# Bluetooth_NRF.net
KiCad netlist of a schematic drawn in Altium Designer
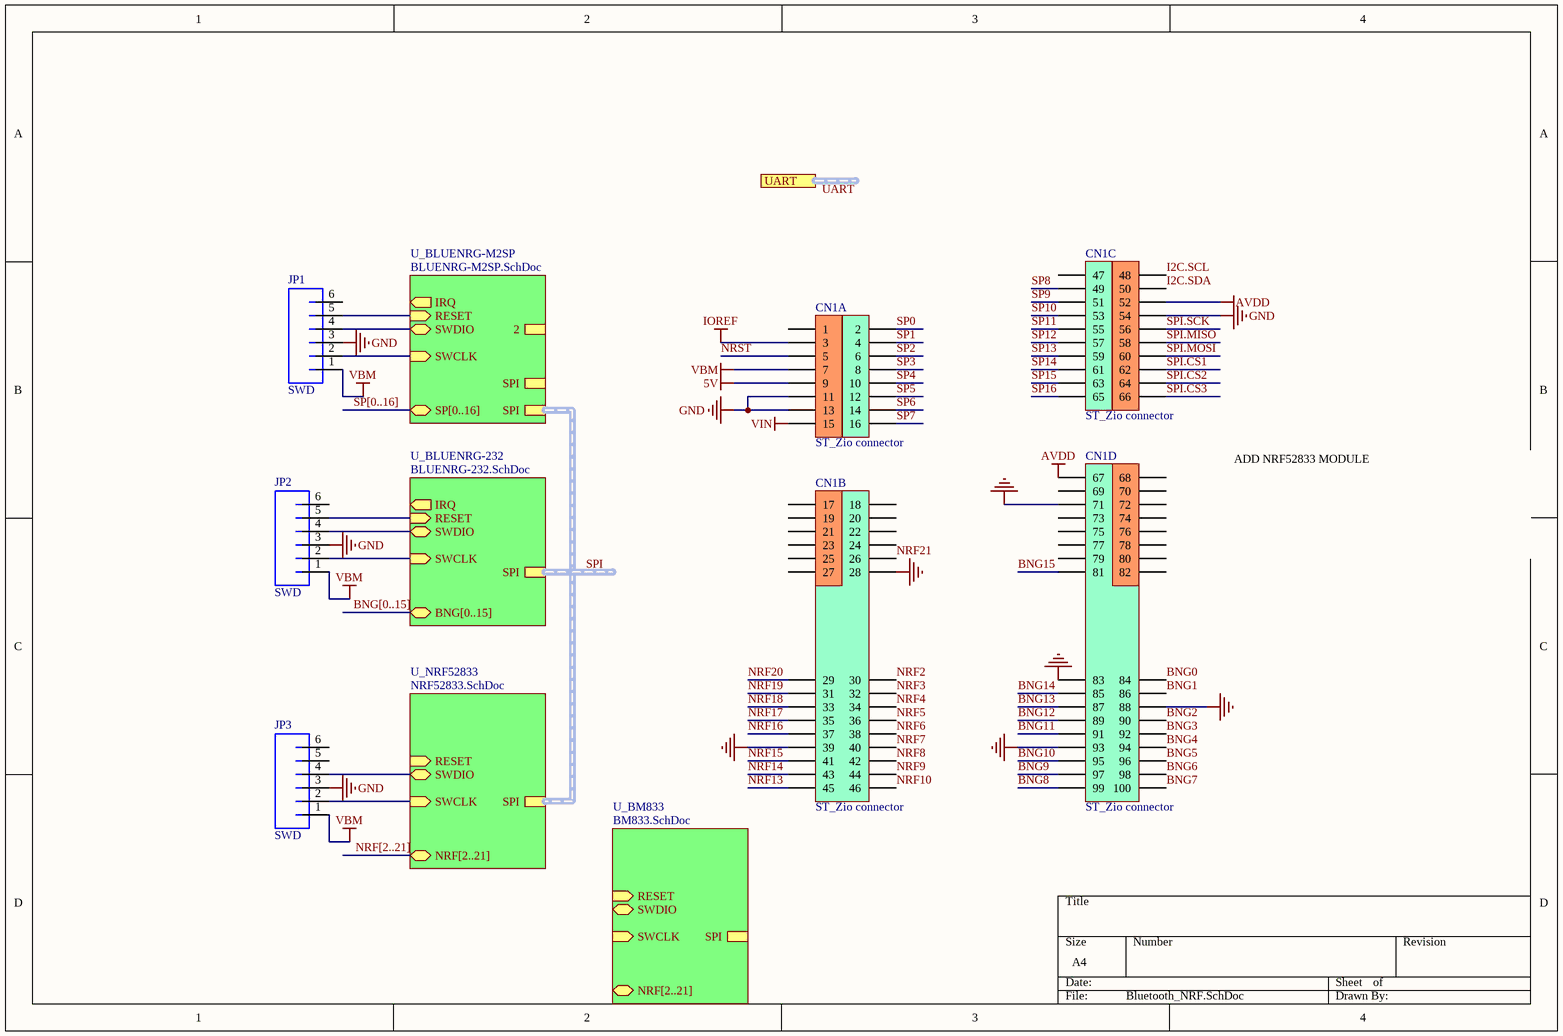
[diagram p0: Bluetooth_NRF.SchDoc]

(export (version "E")
  (design (tool "Eeschema 10.0.6"))
  (components
    (comp (ref "CN1")
      (value "ST_Zio connector")
      (footprint "ST_Zio")
      (libsource (lib "Modules") (part "ST_Zio connector"))
    )
    (comp (ref "JP1")
      (value "SWD")
      (footprint "MOLEX_5045_6")
      (fields
        (field (name "PARTNUMBER") "B6B-PH-K-S(LF)(SN)")
        (field (name "MANUFACTURER") "JST Sales America Inc.")
      )
      (libsource (lib "Connectors") (part "MOLEX_5045_6"))
    )
    (comp (ref "JP2")
      (value "SWD")
      (footprint "MOLEX_5045_6")
      (fields
        (field (name "PARTNUMBER") "B6B-PH-K-S(LF)(SN)")
        (field (name "MANUFACTURER") "JST Sales America Inc.")
      )
      (libsource (lib "Connectors") (part "MOLEX_5045_6"))
    )
    (comp (ref "JP3")
      (value "SWD")
      (footprint "MOLEX_5045_6")
      (fields
        (field (name "PARTNUMBER") "B6B-PH-K-S(LF)(SN)")
        (field (name "MANUFACTURER") "JST Sales America Inc.")
      )
      (libsource (lib "Connectors") (part "MOLEX_5045_6"))
    )
  )
  (nets
    (net (code "6") (name "/BNG0") (class "Default")
      (node (ref "CN1") (pin "84") (pinfunction "84_84") (pintype "passive"))
    )
    (net (code "7") (name "/BNG1") (class "Default")
      (node (ref "CN1") (pin "86") (pinfunction "86_86") (pintype "passive"))
    )
    (net (code "8") (name "/BNG2") (class "Default")
      (node (ref "CN1") (pin "90") (pinfunction "90_90") (pintype "passive"))
    )
    (net (code "9") (name "/BNG3") (class "Default")
      (node (ref "CN1") (pin "92") (pinfunction "92_92") (pintype "passive"))
    )
    (net (code "10") (name "/BNG4") (class "Default")
      (node (ref "CN1") (pin "94") (pinfunction "94_94") (pintype "passive"))
    )
    (net (code "11") (name "/BNG5") (class "Default")
      (node (ref "CN1") (pin "96") (pinfunction "96_96") (pintype "passive"))
    )
    (net (code "12") (name "/BNG6") (class "Default")
      (node (ref "CN1") (pin "98") (pinfunction "98_98") (pintype "passive"))
    )
    (net (code "13") (name "/BNG7") (class "Default")
      (node (ref "CN1") (pin "100") (pinfunction "100_100") (pintype "passive"))
    )
    (net (code "14") (name "/BNG8") (class "Default")
      (node (ref "CN1") (pin "99") (pinfunction "99_99") (pintype "passive"))
    )
    (net (code "15") (name "/BNG9") (class "Default")
      (node (ref "CN1") (pin "97") (pinfunction "97_97") (pintype "passive"))
    )
    (net (code "16") (name "/BNG10") (class "Default")
      (node (ref "CN1") (pin "95") (pinfunction "95_95") (pintype "passive"))
    )
    (net (code "17") (name "/BNG11") (class "Default")
      (node (ref "CN1") (pin "91") (pinfunction "91_91") (pintype "passive"))
    )
    (net (code "18") (name "/BNG12") (class "Default")
      (node (ref "CN1") (pin "89") (pinfunction "89_89") (pintype "passive"))
    )
    (net (code "19") (name "/BNG13") (class "Default")
      (node (ref "CN1") (pin "87") (pinfunction "87_87") (pintype "passive"))
    )
    (net (code "20") (name "/BNG14") (class "Default")
      (node (ref "CN1") (pin "85") (pinfunction "85_85") (pintype "passive"))
    )
    (net (code "21") (name "/BNG15") (class "Default")
      (node (ref "CN1") (pin "81") (pinfunction "81_81") (pintype "passive"))
    )
    (net (code "23") (name "/I2C.SCL") (class "Default")
      (node (ref "CN1") (pin "48") (pinfunction "48_48") (pintype "passive"))
    )
    (net (code "24") (name "/I2C.SDA") (class "Default")
      (node (ref "CN1") (pin "50") (pinfunction "50_50") (pintype "passive"))
    )
    (net (code "27") (name "/NRF2") (class "Default")
      (node (ref "CN1") (pin "30") (pinfunction "30_30") (pintype "passive"))
    )
    (net (code "28") (name "/NRF3") (class "Default")
      (node (ref "CN1") (pin "32") (pinfunction "32_32") (pintype "passive"))
    )
    (net (code "29") (name "/NRF4") (class "Default")
      (node (ref "CN1") (pin "34") (pinfunction "34_34") (pintype "passive"))
    )
    (net (code "30") (name "/NRF5") (class "Default")
      (node (ref "CN1") (pin "36") (pinfunction "36_36") (pintype "passive"))
    )
    (net (code "31") (name "/NRF6") (class "Default")
      (node (ref "CN1") (pin "38") (pinfunction "38_38") (pintype "passive"))
    )
    (net (code "32") (name "/NRF7") (class "Default")
      (node (ref "CN1") (pin "40") (pinfunction "40_40") (pintype "passive"))
    )
    (net (code "33") (name "/NRF8") (class "Default")
      (node (ref "CN1") (pin "42") (pinfunction "42_42") (pintype "passive"))
    )
    (net (code "34") (name "/NRF9") (class "Default")
      (node (ref "CN1") (pin "44") (pinfunction "44_44") (pintype "passive"))
    )
    (net (code "35") (name "/NRF10") (class "Default")
      (node (ref "CN1") (pin "46") (pinfunction "46_46") (pintype "passive"))
    )
    (net (code "36") (name "/NRF13") (class "Default")
      (node (ref "CN1") (pin "45") (pinfunction "45_45") (pintype "passive"))
    )
    (net (code "37") (name "/NRF14") (class "Default")
      (node (ref "CN1") (pin "43") (pinfunction "43_43") (pintype "passive"))
    )
    (net (code "38") (name "/NRF15") (class "Default")
      (node (ref "CN1") (pin "41") (pinfunction "41_41") (pintype "passive"))
    )
    (net (code "39") (name "/NRF16") (class "Default")
      (node (ref "CN1") (pin "37") (pinfunction "37_37") (pintype "passive"))
    )
    (net (code "40") (name "/NRF17") (class "Default")
      (node (ref "CN1") (pin "35") (pinfunction "35_35") (pintype "passive"))
    )
    (net (code "41") (name "/NRF18") (class "Default")
      (node (ref "CN1") (pin "33") (pinfunction "33_33") (pintype "passive"))
    )
    (net (code "42") (name "/NRF19") (class "Default")
      (node (ref "CN1") (pin "31") (pinfunction "31_31") (pintype "passive"))
    )
    (net (code "43") (name "/NRF20") (class "Default")
      (node (ref "CN1") (pin "29") (pinfunction "29_29") (pintype "passive"))
    )
    (net (code "44") (name "/NRF21") (class "Default")
      (node (ref "CN1") (pin "26") (pinfunction "26_26") (pintype "passive"))
    )
    (net (code "47") (name "/NRST") (class "Default")
      (node (ref "CN1") (pin "5") (pinfunction "5_5") (pintype "passive"))
    )
    (net (code "50") (name "/RESET_2") (class "Default")
      (node (ref "JP1") (pin "5") (pinfunction "5_5") (pintype "passive"))
    )
    (net (code "51") (name "/RESET_3") (class "Default")
      (node (ref "JP2") (pin "5") (pinfunction "5_5") (pintype "passive"))
    )
    (net (code "52") (name "/SP0") (class "Default")
      (node (ref "CN1") (pin "2") (pinfunction "2_2") (pintype "passive"))
    )
    (net (code "53") (name "/SP1") (class "Default")
      (node (ref "CN1") (pin "4") (pinfunction "4_4") (pintype "passive"))
    )
    (net (code "54") (name "/SP2") (class "Default")
      (node (ref "CN1") (pin "6") (pinfunction "6_6") (pintype "passive"))
    )
    (net (code "55") (name "/SP3") (class "Default")
      (node (ref "CN1") (pin "8") (pinfunction "8_8") (pintype "passive"))
    )
    (net (code "56") (name "/SP4") (class "Default")
      (node (ref "CN1") (pin "10") (pinfunction "10_10") (pintype "passive"))
    )
    (net (code "57") (name "/SP5") (class "Default")
      (node (ref "CN1") (pin "12") (pinfunction "12_12") (pintype "passive"))
    )
    (net (code "58") (name "/SP6") (class "Default")
      (node (ref "CN1") (pin "14") (pinfunction "14_14") (pintype "passive"))
    )
    (net (code "59") (name "/SP7") (class "Default")
      (node (ref "CN1") (pin "16") (pinfunction "16_16") (pintype "passive"))
    )
    (net (code "60") (name "/SP8") (class "Default")
      (node (ref "CN1") (pin "49") (pinfunction "49_49") (pintype "passive"))
    )
    (net (code "61") (name "/SP9") (class "Default")
      (node (ref "CN1") (pin "51") (pinfunction "51_51") (pintype "passive"))
    )
    (net (code "62") (name "/SP10") (class "Default")
      (node (ref "CN1") (pin "53") (pinfunction "53_53") (pintype "passive"))
    )
    (net (code "63") (name "/SP11") (class "Default")
      (node (ref "CN1") (pin "55") (pinfunction "55_55") (pintype "passive"))
    )
    (net (code "64") (name "/SP12") (class "Default")
      (node (ref "CN1") (pin "57") (pinfunction "57_57") (pintype "passive"))
    )
    (net (code "65") (name "/SP13") (class "Default")
      (node (ref "CN1") (pin "59") (pinfunction "59_59") (pintype "passive"))
    )
    (net (code "66") (name "/SP14") (class "Default")
      (node (ref "CN1") (pin "61") (pinfunction "61_61") (pintype "passive"))
    )
    (net (code "67") (name "/SP15") (class "Default")
      (node (ref "CN1") (pin "63") (pinfunction "63_63") (pintype "passive"))
    )
    (net (code "68") (name "/SP16") (class "Default")
      (node (ref "CN1") (pin "65") (pinfunction "65_65") (pintype "passive"))
    )
    (net (code "70") (name "/SPI.CS1") (class "Default")
      (node (ref "CN1") (pin "62") (pinfunction "62_62") (pintype "passive"))
    )
    (net (code "71") (name "/SPI.CS2") (class "Default")
      (node (ref "CN1") (pin "64") (pinfunction "64_64") (pintype "passive"))
    )
    (net (code "72") (name "/SPI.CS3") (class "Default")
      (node (ref "CN1") (pin "66") (pinfunction "66_66") (pintype "passive"))
    )
    (net (code "73") (name "/SPI.MISO") (class "Default")
      (node (ref "CN1") (pin "58") (pinfunction "58_58") (pintype "passive"))
    )
    (net (code "74") (name "/SPI.MOSI") (class "Default")
      (node (ref "CN1") (pin "60") (pinfunction "60_60") (pintype "passive"))
    )
    (net (code "75") (name "/SPI.SCK") (class "Default")
      (node (ref "CN1") (pin "56") (pinfunction "56_56") (pintype "passive"))
    )
    (net (code "79") (name "/SWCLK_1") (class "Default")
      (node (ref "JP3") (pin "2") (pinfunction "2_2") (pintype "passive"))
    )
    (net (code "80") (name "/SWCLK_2") (class "Default")
      (node (ref "JP1") (pin "2") (pinfunction "2_2") (pintype "passive"))
    )
    (net (code "81") (name "/SWCLK_3") (class "Default")
      (node (ref "JP2") (pin "2") (pinfunction "2_2") (pintype "passive"))
    )
    (net (code "83") (name "/SWDIO_1") (class "Default")
      (node (ref "JP3") (pin "4") (pinfunction "4_4") (pintype "passive"))
    )
    (net (code "84") (name "/SWDIO_2") (class "Default")
      (node (ref "JP1") (pin "4") (pinfunction "4_4") (pintype "passive"))
    )
    (net (code "85") (name "/SWDIO_3") (class "Default")
      (node (ref "JP2") (pin "4") (pinfunction "4_4") (pintype "passive"))
    )
    (net (code "88") (name "5V") (class "Default")
      (node (ref "CN1") (pin "9") (pinfunction "9_9") (pintype "passive"))
    )
    (net (code "89") (name "AVDD") (class "Default")
      (node (ref "CN1") (pin "52") (pinfunction "52_52") (pintype "passive"))
      (node (ref "CN1") (pin "67") (pinfunction "67_67") (pintype "passive"))
    )
    (net (code "90") (name "GND") (class "Default")
      (node (ref "CN1") (pin "11") (pinfunction "11_11") (pintype "passive"))
      (node (ref "CN1") (pin "13") (pinfunction "13_13") (pintype "passive"))
      (node (ref "CN1") (pin "28") (pinfunction "28_28") (pintype "passive"))
      (node (ref "CN1") (pin "39") (pinfunction "39_39") (pintype "passive"))
      (node (ref "CN1") (pin "54") (pinfunction "54_54") (pintype "passive"))
      (node (ref "CN1") (pin "71") (pinfunction "71_71") (pintype "passive"))
      (node (ref "CN1") (pin "83") (pinfunction "83_83") (pintype "passive"))
      (node (ref "CN1") (pin "88") (pinfunction "88_88") (pintype "passive"))
      (node (ref "CN1") (pin "93") (pinfunction "93_93") (pintype "passive"))
      (node (ref "JP1") (pin "3") (pinfunction "3_3") (pintype "passive"))
      (node (ref "JP2") (pin "3") (pinfunction "3_3") (pintype "passive"))
      (node (ref "JP3") (pin "3") (pinfunction "3_3") (pintype "passive"))
    )
    (net (code "91") (name "IOREF") (class "Default")
      (node (ref "CN1") (pin "3") (pinfunction "3_3") (pintype "passive"))
    )
    (net (code "92") (name "VBM") (class "Default")
      (node (ref "CN1") (pin "7") (pinfunction "7_7") (pintype "passive"))
      (node (ref "JP1") (pin "1") (pinfunction "1_1") (pintype "passive"))
      (node (ref "JP2") (pin "1") (pinfunction "1_1") (pintype "passive"))
      (node (ref "JP3") (pin "1") (pinfunction "1_1") (pintype "passive"))
    )
    (net (code "93") (name "VIN") (class "Default")
      (node (ref "CN1") (pin "15") (pinfunction "15_15") (pintype "passive"))
    )
    (net (code "94") (name "unconnected-(CN1-Pad1)") (class "Default")
      (node (ref "CN1") (pin "1") (pinfunction "1_1") (pintype "passive"))
    )
    (net (code "95") (name "unconnected-(CN1-Pad17)") (class "Default")
      (node (ref "CN1") (pin "17") (pinfunction "17_17") (pintype "passive"))
    )
    (net (code "96") (name "unconnected-(CN1-Pad18)") (class "Default")
      (node (ref "CN1") (pin "18") (pinfunction "18_18") (pintype "passive"))
    )
    (net (code "97") (name "unconnected-(CN1-Pad19)") (class "Default")
      (node (ref "CN1") (pin "19") (pinfunction "19_19") (pintype "passive"))
    )
    (net (code "98") (name "unconnected-(CN1-Pad20)") (class "Default")
      (node (ref "CN1") (pin "20") (pinfunction "20_20") (pintype "passive"))
    )
    (net (code "99") (name "unconnected-(CN1-Pad21)") (class "Default")
      (node (ref "CN1") (pin "21") (pinfunction "21_21") (pintype "passive"))
    )
    (net (code "100") (name "unconnected-(CN1-Pad22)") (class "Default")
      (node (ref "CN1") (pin "22") (pinfunction "22_22") (pintype "passive"))
    )
    (net (code "101") (name "unconnected-(CN1-Pad23)") (class "Default")
      (node (ref "CN1") (pin "23") (pinfunction "23_23") (pintype "passive"))
    )
    (net (code "102") (name "unconnected-(CN1-Pad24)") (class "Default")
      (node (ref "CN1") (pin "24") (pinfunction "24_24") (pintype "passive"))
    )
    (net (code "103") (name "unconnected-(CN1-Pad25)") (class "Default")
      (node (ref "CN1") (pin "25") (pinfunction "25_25") (pintype "passive"))
    )
    (net (code "104") (name "unconnected-(CN1-Pad27)") (class "Default")
      (node (ref "CN1") (pin "27") (pinfunction "27_27") (pintype "passive"))
    )
    (net (code "105") (name "unconnected-(CN1-Pad47)") (class "Default")
      (node (ref "CN1") (pin "47") (pinfunction "47_47") (pintype "passive"))
    )
    (net (code "106") (name "unconnected-(CN1-Pad68)") (class "Default")
      (node (ref "CN1") (pin "68") (pinfunction "68_68") (pintype "passive"))
    )
    (net (code "107") (name "unconnected-(CN1-Pad69)") (class "Default")
      (node (ref "CN1") (pin "69") (pinfunction "69_69") (pintype "passive"))
    )
    (net (code "108") (name "unconnected-(CN1-Pad70)") (class "Default")
      (node (ref "CN1") (pin "70") (pinfunction "70_70") (pintype "passive"))
    )
    (net (code "109") (name "unconnected-(CN1-Pad72)") (class "Default")
      (node (ref "CN1") (pin "72") (pinfunction "72_72") (pintype "passive"))
    )
    (net (code "110") (name "unconnected-(CN1-Pad73)") (class "Default")
      (node (ref "CN1") (pin "73") (pinfunction "73_73") (pintype "passive"))
    )
    (net (code "111") (name "unconnected-(CN1-Pad74)") (class "Default")
      (node (ref "CN1") (pin "74") (pinfunction "74_74") (pintype "passive"))
    )
    (net (code "112") (name "unconnected-(CN1-Pad75)") (class "Default")
      (node (ref "CN1") (pin "75") (pinfunction "75_75") (pintype "passive"))
    )
    (net (code "113") (name "unconnected-(CN1-Pad76)") (class "Default")
      (node (ref "CN1") (pin "76") (pinfunction "76_76") (pintype "passive"))
    )
    (net (code "114") (name "unconnected-(CN1-Pad77)") (class "Default")
      (node (ref "CN1") (pin "77") (pinfunction "77_77") (pintype "passive"))
    )
    (net (code "115") (name "unconnected-(CN1-Pad78)") (class "Default")
      (node (ref "CN1") (pin "78") (pinfunction "78_78") (pintype "passive"))
    )
    (net (code "116") (name "unconnected-(CN1-Pad79)") (class "Default")
      (node (ref "CN1") (pin "79") (pinfunction "79_79") (pintype "passive"))
    )
    (net (code "117") (name "unconnected-(CN1-Pad80)") (class "Default")
      (node (ref "CN1") (pin "80") (pinfunction "80_80") (pintype "passive"))
    )
    (net (code "118") (name "unconnected-(CN1-Pad82)") (class "Default")
      (node (ref "CN1") (pin "82") (pinfunction "82_82") (pintype "passive"))
    )
    (net (code "119") (name "unconnected-(JP1-Pad6)") (class "Default")
      (node (ref "JP1") (pin "6") (pinfunction "6_6") (pintype "passive"))
    )
    (net (code "120") (name "unconnected-(JP2-Pad6)") (class "Default")
      (node (ref "JP2") (pin "6") (pinfunction "6_6") (pintype "passive"))
    )
    (net (code "121") (name "unconnected-(JP3-Pad5)") (class "Default")
      (node (ref "JP3") (pin "5") (pinfunction "5_5") (pintype "passive"))
    )
    (net (code "122") (name "unconnected-(JP3-Pad6)") (class "Default")
      (node (ref "JP3") (pin "6") (pinfunction "6_6") (pintype "passive"))
    )
  )
)
